# 11-_--.net
KiCad netlist of a schematic drawn in Altium Designer
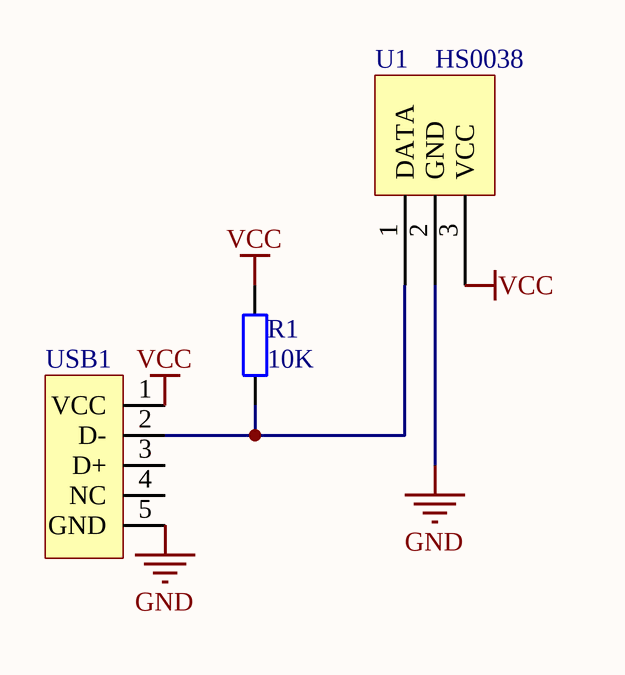
[diagram p0: 11-红外遥控接收器模块--原理图.SchDoc]

(export (version "E")
  (design (tool "Eeschema 10.0.6"))
  (components
    (comp (ref "R1")
      (value "10K")
      (footprint "0805")
      (description "Resistor")
      (fields (field (name "Comment") "res2") (field (name "PUBLISHER") "Altium Limited"))
      (libsource (lib "Miscellaneous Devices") (part "Res2"))
    )
    (comp (ref "U1") (value "HS0038") (footprint "HS0038") (libsource (lib "Schlib1") (part "HS0038")))
    (comp (ref "USB1") (value "USB") (footprint "USB/SM0.8-6H5") (libsource (lib "原理图库") (part "USB5")))
  )
  (nets
    (net (code "1") (name "GND") (class "Default")
      (node (ref "U1") (pin "2") (pinfunction "GND_2") (pintype "passive"))
      (node (ref "USB1") (pin "5") (pinfunction "GND_5") (pintype "passive"))
    )
    (net (code "2") (name "Net-(U1-DATA)") (class "Default")
      (node (ref "R1") (pin "2") (pinfunction "2_2") (pintype "passive"))
      (node (ref "U1") (pin "1") (pinfunction "DATA_1") (pintype "passive"))
      (node (ref "USB1") (pin "2") (pinfunction "D-_2") (pintype "passive"))
    )
    (net (code "3") (name "VCC") (class "Default")
      (node (ref "R1") (pin "1") (pinfunction "1_1") (pintype "passive"))
      (node (ref "U1") (pin "3") (pinfunction "VCC_3") (pintype "passive"))
      (node (ref "USB1") (pin "1") (pinfunction "VCC_1") (pintype "passive"))
    )
    (net (code "4") (name "unconnected-(USB1-D+-Pad3)") (class "Default")
      (node (ref "USB1") (pin "3") (pinfunction "D+_3") (pintype "passive"))
    )
    (net (code "5") (name "unconnected-(USB1-NC-Pad4)") (class "Default")
      (node (ref "USB1") (pin "4") (pinfunction "NC_4") (pintype "passive"))
    )
  )
)
